# sd2_redraw.net
KiCad netlist of a schematic drawn in EAGLE
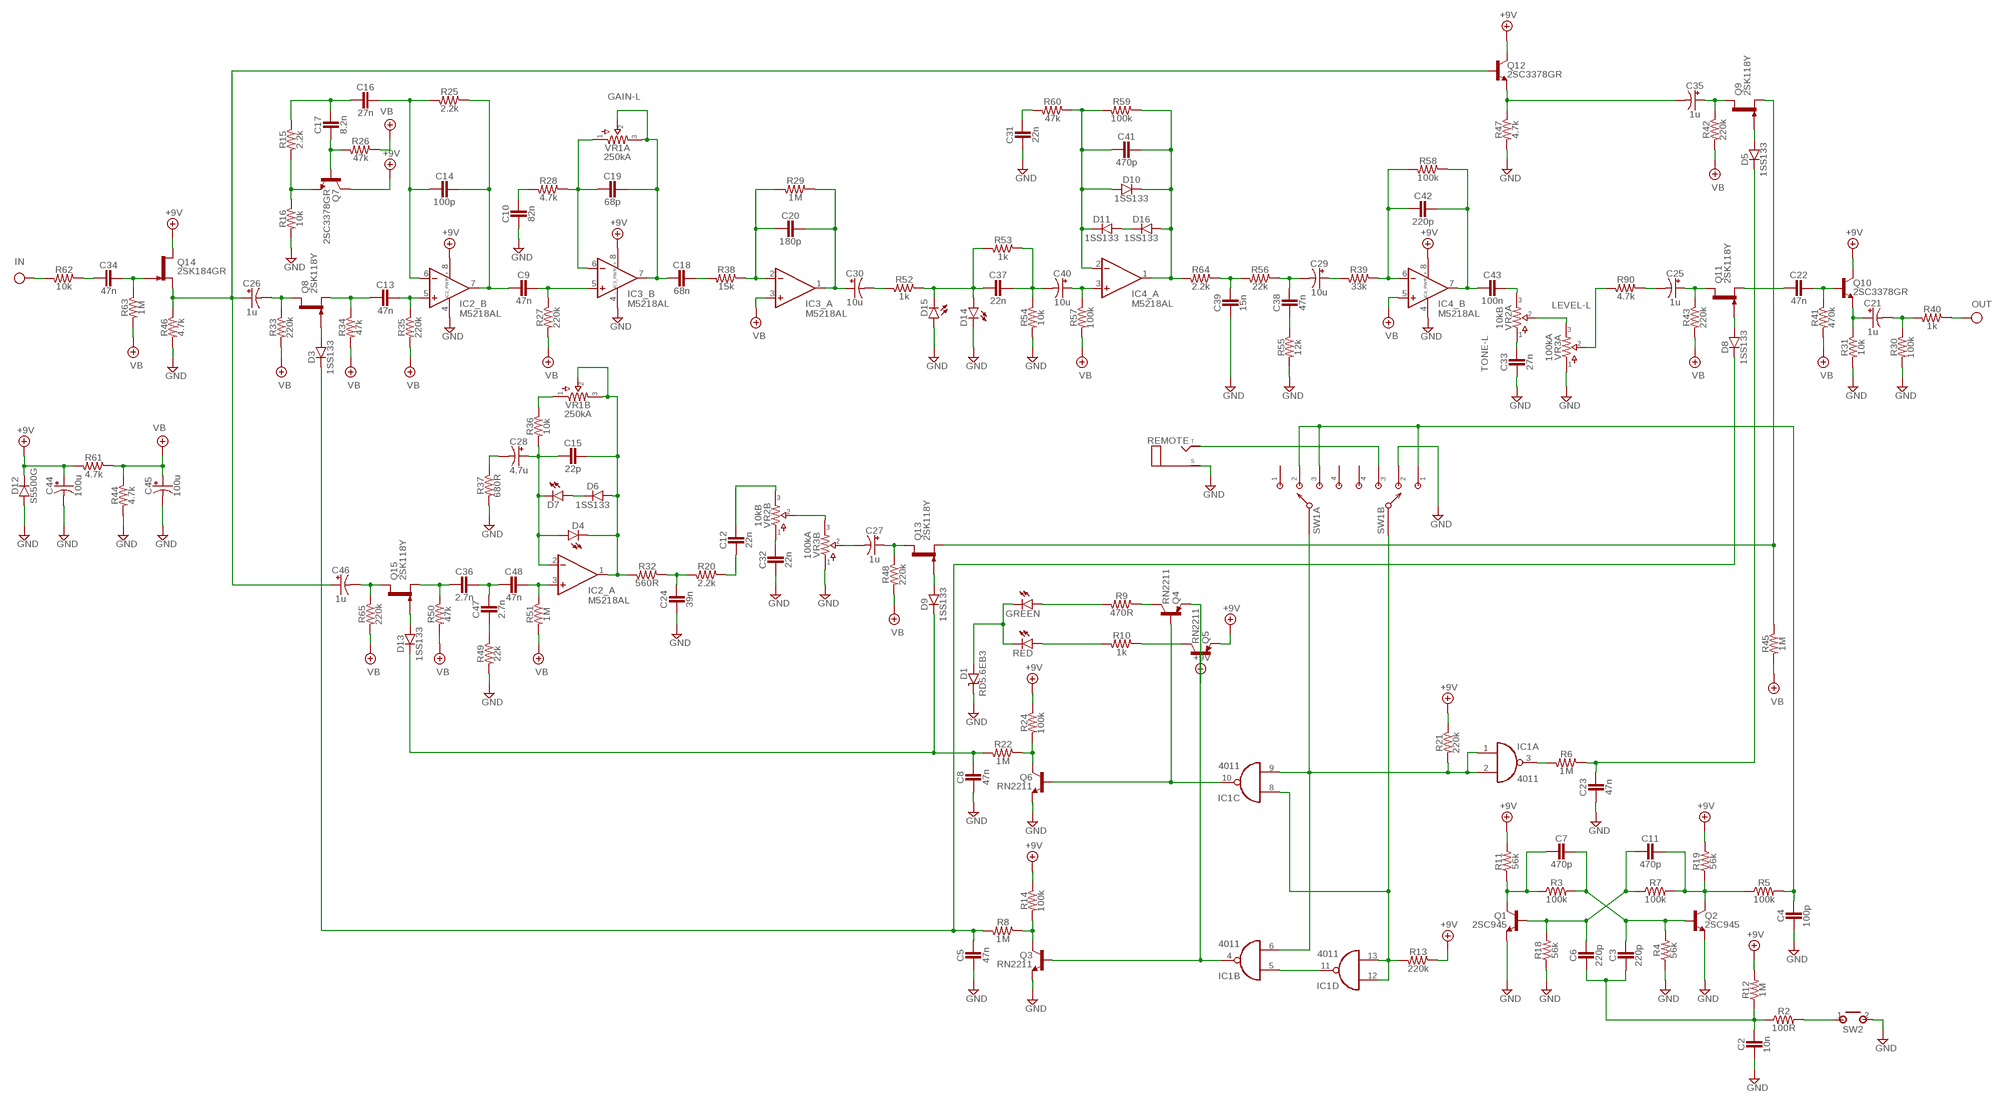
[diagram p0: schematic, sheet 1]

(export (version "E")
  (design (tool "Eeschema 10.0.6"))
  (components
    (comp (ref "C2")
      (value "10n")
      (footprint "eagle-import:BOX_SMALL")
      (libsource (lib "eagle-import") (part "CER/FILMBOX.1"))
    )
    (comp (ref "C3")
      (value "220p")
      (footprint "eagle-import:BOX_SMALL")
      (libsource (lib "eagle-import") (part "CER/FILMBOX.1"))
    )
    (comp (ref "C4")
      (value "100p")
      (footprint "eagle-import:BOX_SMALL")
      (libsource (lib "eagle-import") (part "CER/FILMBOX.1"))
    )
    (comp (ref "C5")
      (value "47n")
      (footprint "eagle-import:BOX_SMALL")
      (libsource (lib "eagle-import") (part "CER/FILMBOX.1"))
    )
    (comp (ref "C6")
      (value "220p")
      (footprint "eagle-import:BOX_SMALL")
      (libsource (lib "eagle-import") (part "CER/FILMBOX.1"))
    )
    (comp (ref "C7")
      (value "470p")
      (footprint "eagle-import:BOX_SMALL")
      (libsource (lib "eagle-import") (part "CER/FILMBOX.1"))
    )
    (comp (ref "C8")
      (value "47n")
      (footprint "eagle-import:BOX_SMALL")
      (libsource (lib "eagle-import") (part "CER/FILMBOX.1"))
    )
    (comp (ref "C9")
      (value "47n")
      (footprint "eagle-import:BOX_SMALL")
      (libsource (lib "eagle-import") (part "CER/FILMBOX.1"))
    )
    (comp (ref "C10")
      (value "82n")
      (footprint "eagle-import:BOX_SMALL")
      (libsource (lib "eagle-import") (part "CER/FILMBOX.1"))
    )
    (comp (ref "C11")
      (value "470p")
      (footprint "eagle-import:BOX_SMALL")
      (libsource (lib "eagle-import") (part "CER/FILMBOX.1"))
    )
    (comp (ref "C12")
      (value "22n")
      (footprint "eagle-import:BOX_SMALL")
      (libsource (lib "eagle-import") (part "CER/FILMBOX.1"))
    )
    (comp (ref "C13")
      (value "47n")
      (footprint "eagle-import:BOX_SMALL")
      (libsource (lib "eagle-import") (part "CER/FILMBOX.1"))
    )
    (comp (ref "C14")
      (value "100p")
      (footprint "eagle-import:BOX_SMALL")
      (libsource (lib "eagle-import") (part "CER/FILMBOX.1"))
    )
    (comp (ref "C15")
      (value "22p")
      (footprint "eagle-import:BOX_SMALL")
      (libsource (lib "eagle-import") (part "CER/FILMBOX.1"))
    )
    (comp (ref "C16")
      (value "27n")
      (footprint "eagle-import:BOX_SMALL")
      (libsource (lib "eagle-import") (part "CER/FILMBOX.1"))
    )
    (comp (ref "C17")
      (value "8.2n")
      (footprint "eagle-import:BOX_SMALL")
      (libsource (lib "eagle-import") (part "CER/FILMBOX.1"))
    )
    (comp (ref "C18")
      (value "68n")
      (footprint "eagle-import:BOX_SMALL")
      (libsource (lib "eagle-import") (part "CER/FILMBOX.1"))
    )
    (comp (ref "C19")
      (value "68p")
      (footprint "eagle-import:BOX_SMALL")
      (libsource (lib "eagle-import") (part "CER/FILMBOX.1"))
    )
    (comp (ref "C20")
      (value "180p")
      (footprint "eagle-import:BOX_SMALL")
      (libsource (lib "eagle-import") (part "CER/FILMBOX.1"))
    )
    (comp (ref "C21")
      (value "1u")
      (footprint "eagle-import:040_020")
      (libsource (lib "eagle-import") (part "0400"))
    )
    (comp (ref "C22")
      (value "47n")
      (footprint "eagle-import:BOX_SMALL")
      (libsource (lib "eagle-import") (part "CER/FILMBOX.1"))
    )
    (comp (ref "C23")
      (value "47n")
      (footprint "eagle-import:BOX_SMALL")
      (libsource (lib "eagle-import") (part "CER/FILMBOX.1"))
    )
    (comp (ref "C24")
      (value "39n")
      (footprint "eagle-import:BOX_SMALL")
      (libsource (lib "eagle-import") (part "CER/FILMBOX.1"))
    )
    (comp (ref "C25")
      (value "1u")
      (footprint "eagle-import:040_020")
      (libsource (lib "eagle-import") (part "0400"))
    )
    (comp (ref "C26")
      (value "1u")
      (footprint "eagle-import:040_020")
      (libsource (lib "eagle-import") (part "0400"))
    )
    (comp (ref "C27")
      (value "1u")
      (footprint "eagle-import:040_020")
      (libsource (lib "eagle-import") (part "0400"))
    )
    (comp (ref "C28")
      (value "4.7u")
      (footprint "eagle-import:040_020")
      (libsource (lib "eagle-import") (part "0400"))
    )
    (comp (ref "C29")
      (value "10u")
      (footprint "eagle-import:040_020")
      (libsource (lib "eagle-import") (part "0400"))
    )
    (comp (ref "C30")
      (value "10u")
      (footprint "eagle-import:040_020")
      (libsource (lib "eagle-import") (part "0400"))
    )
    (comp (ref "C31")
      (value "22n")
      (footprint "eagle-import:BOX_SMALL")
      (libsource (lib "eagle-import") (part "CER/FILMBOX.1"))
    )
    (comp (ref "C32")
      (value "22n")
      (footprint "eagle-import:BOX_SMALL")
      (libsource (lib "eagle-import") (part "CER/FILMBOX.1"))
    )
    (comp (ref "C33")
      (value "27n")
      (footprint "eagle-import:BOX_SMALL")
      (libsource (lib "eagle-import") (part "CER/FILMBOX.1"))
    )
    (comp (ref "C34")
      (value "47n")
      (footprint "eagle-import:BOX_SMALL")
      (libsource (lib "eagle-import") (part "CER/FILMBOX.1"))
    )
    (comp (ref "C35")
      (value "1u")
      (footprint "eagle-import:040_020")
      (libsource (lib "eagle-import") (part "0400"))
    )
    (comp (ref "C36")
      (value "2.7n")
      (footprint "eagle-import:BOX_SMALL")
      (libsource (lib "eagle-import") (part "CER/FILMBOX.1"))
    )
    (comp (ref "C37")
      (value "22n")
      (footprint "eagle-import:BOX_SMALL")
      (libsource (lib "eagle-import") (part "CER/FILMBOX.1"))
    )
    (comp (ref "C38")
      (value "47n")
      (footprint "eagle-import:BOX_SMALL")
      (libsource (lib "eagle-import") (part "CER/FILMBOX.1"))
    )
    (comp (ref "C39")
      (value "15n")
      (footprint "eagle-import:BOX_SMALL")
      (libsource (lib "eagle-import") (part "CER/FILMBOX.1"))
    )
    (comp (ref "C40")
      (value "10u")
      (footprint "eagle-import:040_020")
      (libsource (lib "eagle-import") (part "0400"))
    )
    (comp (ref "C41")
      (value "470p")
      (footprint "eagle-import:BOX_SMALL")
      (libsource (lib "eagle-import") (part "CER/FILMBOX.1"))
    )
    (comp (ref "C42")
      (value "220p")
      (footprint "eagle-import:BOX_SMALL")
      (libsource (lib "eagle-import") (part "CER/FILMBOX.1"))
    )
    (comp (ref "C43")
      (value "100n")
      (footprint "eagle-import:BOX_SMALL")
      (libsource (lib "eagle-import") (part "CER/FILMBOX.1"))
    )
    (comp (ref "C44")
      (value "100u")
      (footprint "eagle-import:040_020")
      (libsource (lib "eagle-import") (part "0400"))
    )
    (comp (ref "C45")
      (value "100u")
      (footprint "eagle-import:040_020")
      (libsource (lib "eagle-import") (part "0400"))
    )
    (comp (ref "C46")
      (value "1u")
      (footprint "eagle-import:040_020")
      (libsource (lib "eagle-import") (part "0400"))
    )
    (comp (ref "C47")
      (value "2.7n")
      (footprint "eagle-import:BOX_SMALL")
      (libsource (lib "eagle-import") (part "CER/FILMBOX.1"))
    )
    (comp (ref "C48")
      (value "47n")
      (footprint "eagle-import:BOX_SMALL")
      (libsource (lib "eagle-import") (part "CER/FILMBOX.1"))
    )
    (comp (ref "D1")
      (value "RD5.6EB3")
      (footprint "eagle-import:DO41-2")
      (libsource (lib "eagle-import") (part "ZENER.2"))
    )
    (comp (ref "D3")
      (value "1SS133")
      (footprint "eagle-import:DO35-2")
      (libsource (lib "eagle-import") (part "DO35.2"))
    )
    (comp (ref "D4")
      (value "LED")
      (footprint "eagle-import:3MM_D")
      (libsource (lib "eagle-import") (part "LED"))
    )
    (comp (ref "D5")
      (value "1SS133")
      (footprint "eagle-import:DO35-2")
      (libsource (lib "eagle-import") (part "DO35.2"))
    )
    (comp (ref "D6")
      (value "1SS133")
      (footprint "eagle-import:DO35-2")
      (libsource (lib "eagle-import") (part "DO35.2"))
    )
    (comp (ref "D7")
      (value "LED")
      (footprint "eagle-import:3MM_D")
      (libsource (lib "eagle-import") (part "LED"))
    )
    (comp (ref "D8")
      (value "1SS133")
      (footprint "eagle-import:DO35-2")
      (libsource (lib "eagle-import") (part "DO35.2"))
    )
    (comp (ref "D9")
      (value "1SS133")
      (footprint "eagle-import:DO35-2")
      (libsource (lib "eagle-import") (part "DO35.2"))
    )
    (comp (ref "D10")
      (value "1SS133")
      (footprint "eagle-import:DO35-2")
      (libsource (lib "eagle-import") (part "DO35.2"))
    )
    (comp (ref "D11")
      (value "1SS133")
      (footprint "eagle-import:DO35-2")
      (libsource (lib "eagle-import") (part "DO35.2"))
    )
    (comp (ref "D12")
      (value "S5500G")
      (footprint "eagle-import:DO35-2")
      (libsource (lib "eagle-import") (part "DO35.2"))
    )
    (comp (ref "D13")
      (value "1SS133")
      (footprint "eagle-import:DO35-2")
      (libsource (lib "eagle-import") (part "DO35.2"))
    )
    (comp (ref "D14")
      (value "LED")
      (footprint "eagle-import:3MM_D")
      (libsource (lib "eagle-import") (part "LED"))
    )
    (comp (ref "D15")
      (value "LED")
      (footprint "eagle-import:3MM_D")
      (libsource (lib "eagle-import") (part "LED"))
    )
    (comp (ref "D16")
      (value "1SS133")
      (footprint "eagle-import:DO35-2")
      (libsource (lib "eagle-import") (part "DO35.2"))
    )
    (comp (ref "GREEN")
      (value "LED")
      (footprint "eagle-import:3MM_D")
      (libsource (lib "eagle-import") (part "LED"))
    )
    (comp (ref "IC1")
      (value "4011")
      (footprint "eagle-import:DIL14")
      (libsource (lib "eagle-import") (part "4011N"))
    )
    (comp (ref "IC2")
      (value "M5218AL")
      (footprint "eagle-import:DIL0")
      (libsource (lib "eagle-import") (part "DUALTH"))
    )
    (comp (ref "IC3")
      (value "M5218AL")
      (footprint "eagle-import:DIL0")
      (libsource (lib "eagle-import") (part "DUALTH"))
    )
    (comp (ref "IC4")
      (value "M5218AL")
      (footprint "eagle-import:DIL0")
      (libsource (lib "eagle-import") (part "DUALTH"))
    )
    (comp (ref "Q1")
      (value "2SC945")
      (footprint "eagle-import:TO92-")
      (libsource (lib "eagle-import") (part "2SC828A"))
    )
    (comp (ref "Q2")
      (value "2SC945")
      (footprint "eagle-import:TO92-")
      (libsource (lib "eagle-import") (part "2SC828A"))
    )
    (comp (ref "Q3")
      (value "RN2211")
      (footprint "eagle-import:TO92-")
      (libsource (lib "eagle-import") (part "2N3904"))
    )
    (comp (ref "Q4")
      (value "RN2211")
      (footprint "eagle-import:TO92")
      (libsource (lib "eagle-import") (part "2N3906"))
    )
    (comp (ref "Q5")
      (value "RN2211")
      (footprint "eagle-import:TO92")
      (libsource (lib "eagle-import") (part "2N3906"))
    )
    (comp (ref "Q6")
      (value "RN2211")
      (footprint "eagle-import:TO92-")
      (libsource (lib "eagle-import") (part "2N3904"))
    )
    (comp (ref "Q7")
      (value "2SC3378GR")
      (footprint "eagle-import:TO92-")
      (libsource (lib "eagle-import") (part "2N3904"))
    )
    (comp (ref "Q8")
      (value "2SK118Y")
      (footprint "eagle-import:TO92-")
      (libsource (lib "eagle-import") (part "2N5457"))
    )
    (comp (ref "Q9")
      (value "2SK118Y")
      (footprint "eagle-import:TO92-")
      (libsource (lib "eagle-import") (part "2N5457"))
    )
    (comp (ref "Q10")
      (value "2SC3378GR")
      (footprint "eagle-import:TO92-")
      (libsource (lib "eagle-import") (part "2N3904"))
    )
    (comp (ref "Q11")
      (value "2SK118Y")
      (footprint "eagle-import:TO92-")
      (libsource (lib "eagle-import") (part "2N5457"))
    )
    (comp (ref "Q12")
      (value "2SC3378GR")
      (footprint "eagle-import:TO92-")
      (libsource (lib "eagle-import") (part "2N3904"))
    )
    (comp (ref "Q13")
      (value "2SK118Y")
      (footprint "eagle-import:TO92-")
      (libsource (lib "eagle-import") (part "2N5457"))
    )
    (comp (ref "Q14")
      (value "2SK184GR")
      (footprint "eagle-import:TO92-")
      (libsource (lib "eagle-import") (part "2N5457"))
    )
    (comp (ref "Q15")
      (value "2SK118Y")
      (footprint "eagle-import:TO92-")
      (libsource (lib "eagle-import") (part "2N5457"))
    )
    (comp (ref "R2")
      (value "100R")
      (footprint "eagle-import:R0207_3")
      (libsource (lib "eagle-import") (part "R_.3B"))
    )
    (comp (ref "R3")
      (value "100k")
      (footprint "eagle-import:R0207_3")
      (libsource (lib "eagle-import") (part "R_.3B"))
    )
    (comp (ref "R4")
      (value "56k")
      (footprint "eagle-import:R0207_3")
      (libsource (lib "eagle-import") (part "R_.3B"))
    )
    (comp (ref "R5")
      (value "100k")
      (footprint "eagle-import:R0207_3")
      (libsource (lib "eagle-import") (part "R_.3B"))
    )
    (comp (ref "R6")
      (value "1M")
      (footprint "eagle-import:R0207_3")
      (libsource (lib "eagle-import") (part "R_.3B"))
    )
    (comp (ref "R7")
      (value "100k")
      (footprint "eagle-import:R0207_3")
      (libsource (lib "eagle-import") (part "R_.3B"))
    )
    (comp (ref "R8")
      (value "1M")
      (footprint "eagle-import:R0207_3")
      (libsource (lib "eagle-import") (part "R_.3B"))
    )
    (comp (ref "R9")
      (value "470R")
      (footprint "eagle-import:R0207_3")
      (libsource (lib "eagle-import") (part "R_.3B"))
    )
    (comp (ref "R10")
      (value "1k")
      (footprint "eagle-import:R0207_3")
      (libsource (lib "eagle-import") (part "R_.3B"))
    )
    (comp (ref "R11")
      (value "56k")
      (footprint "eagle-import:R0207_3")
      (libsource (lib "eagle-import") (part "R_.3B"))
    )
    (comp (ref "R12")
      (value "1M")
      (footprint "eagle-import:R0207_3")
      (libsource (lib "eagle-import") (part "R_.3B"))
    )
    (comp (ref "R13")
      (value "220k")
      (footprint "eagle-import:R0207_3")
      (libsource (lib "eagle-import") (part "R_.3B"))
    )
    (comp (ref "R14")
      (value "100k")
      (footprint "eagle-import:R0207_3")
      (libsource (lib "eagle-import") (part "R_.3B"))
    )
    (comp (ref "R15")
      (value "2.2k")
      (footprint "eagle-import:R0207_3")
      (libsource (lib "eagle-import") (part "R_.3B"))
    )
    (comp (ref "R16")
      (value "10k")
      (footprint "eagle-import:R0207_3")
      (libsource (lib "eagle-import") (part "R_.3B"))
    )
    (comp (ref "R18")
      (value "56k")
      (footprint "eagle-import:R0207_3")
      (libsource (lib "eagle-import") (part "R_.3B"))
    )
    (comp (ref "R19")
      (value "56k")
      (footprint "eagle-import:R0207_3")
      (libsource (lib "eagle-import") (part "R_.3B"))
    )
    (comp (ref "R20")
      (value "2.2k")
      (footprint "eagle-import:R0207_3")
      (libsource (lib "eagle-import") (part "R_.3B"))
    )
    (comp (ref "R21")
      (value "220k")
      (footprint "eagle-import:R0207_3")
      (libsource (lib "eagle-import") (part "R_.3B"))
    )
    (comp (ref "R22")
      (value "1M")
      (footprint "eagle-import:R0207_3")
      (libsource (lib "eagle-import") (part "R_.3B"))
    )
    (comp (ref "R24")
      (value "100k")
      (footprint "eagle-import:R0207_3")
      (libsource (lib "eagle-import") (part "R_.3B"))
    )
    (comp (ref "R25")
      (value "2.2k")
      (footprint "eagle-import:R0207_3")
      (libsource (lib "eagle-import") (part "R_.3B"))
    )
    (comp (ref "R26")
      (value "47k")
      (footprint "eagle-import:R0207_3")
      (libsource (lib "eagle-import") (part "R_.3B"))
    )
    (comp (ref "R27")
      (value "220k")
      (footprint "eagle-import:R0207_3")
      (libsource (lib "eagle-import") (part "R_.3B"))
    )
    (comp (ref "R28")
      (value "4.7k")
      (footprint "eagle-import:R0207_3")
      (libsource (lib "eagle-import") (part "R_.3B"))
    )
    (comp (ref "R29")
      (value "1M")
      (footprint "eagle-import:R0207_3")
      (libsource (lib "eagle-import") (part "R_.3B"))
    )
    (comp (ref "R30")
      (value "100k")
      (footprint "eagle-import:R0207_3")
      (libsource (lib "eagle-import") (part "R_.3B"))
    )
    (comp (ref "R31")
      (value "10k")
      (footprint "eagle-import:R0207_3")
      (libsource (lib "eagle-import") (part "R_.3B"))
    )
    (comp (ref "R32")
      (value "560R")
      (footprint "eagle-import:R0207_3")
      (libsource (lib "eagle-import") (part "R_.3B"))
    )
    (comp (ref "R33")
      (value "220k")
      (footprint "eagle-import:R0207_3")
      (libsource (lib "eagle-import") (part "R_.3B"))
    )
    (comp (ref "R34")
      (value "47k")
      (footprint "eagle-import:R0207_3")
      (libsource (lib "eagle-import") (part "R_.3B"))
    )
    (comp (ref "R35")
      (value "220k")
      (footprint "eagle-import:R0207_3")
      (libsource (lib "eagle-import") (part "R_.3B"))
    )
    (comp (ref "R36")
      (value "10k")
      (footprint "eagle-import:R0207_3")
      (libsource (lib "eagle-import") (part "R_.3B"))
    )
    (comp (ref "R37")
      (value "680R")
      (footprint "eagle-import:R0207_3")
      (libsource (lib "eagle-import") (part "R_.3B"))
    )
    (comp (ref "R38")
      (value "15k")
      (footprint "eagle-import:R0207_3")
      (libsource (lib "eagle-import") (part "R_.3B"))
    )
    (comp (ref "R39")
      (value "33k")
      (footprint "eagle-import:R0207_3")
      (libsource (lib "eagle-import") (part "R_.3B"))
    )
    (comp (ref "R40")
      (value "1k")
      (footprint "eagle-import:R0207_3")
      (libsource (lib "eagle-import") (part "R_.3B"))
    )
    (comp (ref "R41")
      (value "470k")
      (footprint "eagle-import:R0207_3")
      (libsource (lib "eagle-import") (part "R_.3B"))
    )
    (comp (ref "R42")
      (value "220k")
      (footprint "eagle-import:R0207_3")
      (libsource (lib "eagle-import") (part "R_.3B"))
    )
    (comp (ref "R43")
      (value "220k")
      (footprint "eagle-import:R0207_3")
      (libsource (lib "eagle-import") (part "R_.3B"))
    )
    (comp (ref "R44")
      (value "4.7k")
      (footprint "eagle-import:R0207_3")
      (libsource (lib "eagle-import") (part "R_.3B"))
    )
    (comp (ref "R45")
      (value "1M")
      (footprint "eagle-import:R0207_3")
      (libsource (lib "eagle-import") (part "R_.3B"))
    )
    (comp (ref "R46")
      (value "4.7k")
      (footprint "eagle-import:R0207_3")
      (libsource (lib "eagle-import") (part "R_.3B"))
    )
    (comp (ref "R47")
      (value "4.7k")
      (footprint "eagle-import:R0207_3")
      (libsource (lib "eagle-import") (part "R_.3B"))
    )
    (comp (ref "R48")
      (value "220k")
      (footprint "eagle-import:R0207_3")
      (libsource (lib "eagle-import") (part "R_.3B"))
    )
    (comp (ref "R49")
      (value "22k")
      (footprint "eagle-import:R0207_3")
      (libsource (lib "eagle-import") (part "R_.3B"))
    )
    (comp (ref "R50")
      (value "47k")
      (footprint "eagle-import:R0207_3")
      (libsource (lib "eagle-import") (part "R_.3B"))
    )
    (comp (ref "R51")
      (value "1M")
      (footprint "eagle-import:R0207_3")
      (libsource (lib "eagle-import") (part "R_.3B"))
    )
    (comp (ref "R52")
      (value "1k")
      (footprint "eagle-import:R0207_3")
      (libsource (lib "eagle-import") (part "R_.3B"))
    )
    (comp (ref "R53")
      (value "1k")
      (footprint "eagle-import:R0207_3")
      (libsource (lib "eagle-import") (part "R_.3B"))
    )
    (comp (ref "R54")
      (value "10k")
      (footprint "eagle-import:R0207_3")
      (libsource (lib "eagle-import") (part "R_.3B"))
    )
    (comp (ref "R55")
      (value "12k")
      (footprint "eagle-import:R0207_3")
      (libsource (lib "eagle-import") (part "R_.3B"))
    )
    (comp (ref "R56")
      (value "22k")
      (footprint "eagle-import:R0207_3")
      (libsource (lib "eagle-import") (part "R_.3B"))
    )
    (comp (ref "R57")
      (value "100k")
      (footprint "eagle-import:R0207_3")
      (libsource (lib "eagle-import") (part "R_.3B"))
    )
    (comp (ref "R58")
      (value "100k")
      (footprint "eagle-import:R0207_3")
      (libsource (lib "eagle-import") (part "R_.3B"))
    )
    (comp (ref "R59")
      (value "100k")
      (footprint "eagle-import:R0207_3")
      (libsource (lib "eagle-import") (part "R_.3B"))
    )
    (comp (ref "R60")
      (value "47k")
      (footprint "eagle-import:R0207_3")
      (libsource (lib "eagle-import") (part "R_.3B"))
    )
    (comp (ref "R61")
      (value "4.7k")
      (footprint "eagle-import:R0207_3")
      (libsource (lib "eagle-import") (part "R_.3B"))
    )
    (comp (ref "R62")
      (value "10k")
      (footprint "eagle-import:R0207_3")
      (libsource (lib "eagle-import") (part "R_.3B"))
    )
    (comp (ref "R63")
      (value "1M")
      (footprint "eagle-import:R0207_3")
      (libsource (lib "eagle-import") (part "R_.3B"))
    )
    (comp (ref "R64")
      (value "2.2k")
      (footprint "eagle-import:R0207_3")
      (libsource (lib "eagle-import") (part "R_.3B"))
    )
    (comp (ref "R65")
      (value "220k")
      (footprint "eagle-import:R0207_3")
      (libsource (lib "eagle-import") (part "R_.3B"))
    )
    (comp (ref "R90")
      (value "4.7k")
      (footprint "eagle-import:R0207_3")
      (libsource (lib "eagle-import") (part "R_.3B"))
    )
    (comp (ref "RED")
      (value "LED")
      (footprint "eagle-import:3MM_D")
      (libsource (lib "eagle-import") (part "LED"))
    )
    (comp (ref "REMOTE")
      (value "MONO")
      (footprint "eagle-import:TWO_PADS")
      (libsource (lib "eagle-import") (part "MONO"))
    )
    (comp (ref "SW1")
      (value "2P4T")
      (footprint "eagle-import:SMALLROTARY")
      (libsource (lib "eagle-import") (part "2P4T"))
    )
    (comp (ref "SW2")
      (value "MOMENTARY")
      (footprint "eagle-import:SPST")
      (libsource (lib "eagle-import") (part "MOMENTARY"))
    )
    (comp (ref "VR1A")
      (value "250kA")
      (footprint "eagle-import:16MM")
      (libsource (lib "eagle-import") (part "POTS16MM"))
    )
    (comp (ref "VR1B")
      (value "250kA")
      (footprint "eagle-import:16MM")
      (libsource (lib "eagle-import") (part "POTS16MM"))
    )
    (comp (ref "VR2A")
      (value "10kB")
      (footprint "eagle-import:16MM")
      (libsource (lib "eagle-import") (part "POTS16MM"))
    )
    (comp (ref "VR2B")
      (value "10kB")
      (footprint "eagle-import:16MM")
      (libsource (lib "eagle-import") (part "POTS16MM"))
    )
    (comp (ref "VR3A")
      (value "100kA")
      (footprint "eagle-import:16MM")
      (libsource (lib "eagle-import") (part "POTS16MM"))
    )
    (comp (ref "VR3B")
      (value "100kA")
      (footprint "eagle-import:16MM")
      (libsource (lib "eagle-import") (part "POTS16MM"))
    )
  )
  (nets
    (net (code "1") (name "+9V") (class "Default")
      (node (ref "C44") (pin "+") (pinfunction "+_+") (pintype "passive"))
      (node (ref "D12") (pin "C") (pinfunction "C_C") (pintype "passive"))
      (node (ref "IC2") (pin "8") (pinfunction "V+_8") (pintype "power_in"))
      (node (ref "IC3") (pin "8") (pinfunction "V+_8") (pintype "power_in"))
      (node (ref "IC4") (pin "8") (pinfunction "V+_8") (pintype "power_in"))
      (node (ref "Q10") (pin "1") (pinfunction "C_1") (pintype "passive"))
      (node (ref "Q12") (pin "1") (pinfunction "C_1") (pintype "passive"))
      (node (ref "Q14") (pin "3") (pinfunction "D_3") (pintype "passive"))
      (node (ref "Q4") (pin "3") (pinfunction "E_3") (pintype "passive"))
      (node (ref "Q5") (pin "3") (pinfunction "E_3") (pintype "passive"))
      (node (ref "Q7") (pin "1") (pinfunction "C_1") (pintype "passive"))
      (node (ref "R11") (pin "2") (pinfunction "2_2") (pintype "passive"))
      (node (ref "R12") (pin "2") (pinfunction "2_2") (pintype "passive"))
      (node (ref "R13") (pin "1") (pinfunction "1_1") (pintype "passive"))
      (node (ref "R14") (pin "1") (pinfunction "1_1") (pintype "passive"))
      (node (ref "R19") (pin "2") (pinfunction "2_2") (pintype "passive"))
      (node (ref "R21") (pin "1") (pinfunction "1_1") (pintype "passive"))
      (node (ref "R24") (pin "1") (pinfunction "1_1") (pintype "passive"))
      (node (ref "R61") (pin "2") (pinfunction "2_2") (pintype "passive"))
    )
    (net (code "2") (name "GND") (class "Default")
      (node (ref "C10") (pin "2") (pinfunction "2_2") (pintype "passive"))
      (node (ref "C2") (pin "2") (pinfunction "2_2") (pintype "passive"))
      (node (ref "C23") (pin "2") (pinfunction "2_2") (pintype "passive"))
      (node (ref "C24") (pin "2") (pinfunction "2_2") (pintype "passive"))
      (node (ref "C31") (pin "2") (pinfunction "2_2") (pintype "passive"))
      (node (ref "C32") (pin "2") (pinfunction "2_2") (pintype "passive"))
      (node (ref "C33") (pin "2") (pinfunction "2_2") (pintype "passive"))
      (node (ref "C39") (pin "2") (pinfunction "2_2") (pintype "passive"))
      (node (ref "C4") (pin "2") (pinfunction "2_2") (pintype "passive"))
      (node (ref "C44") (pin "-") (pinfunction "-_-") (pintype "passive"))
      (node (ref "C45") (pin "-") (pinfunction "-_-") (pintype "passive"))
      (node (ref "C5") (pin "2") (pinfunction "2_2") (pintype "passive"))
      (node (ref "C8") (pin "2") (pinfunction "2_2") (pintype "passive"))
      (node (ref "D1") (pin "C") (pinfunction "C_C") (pintype "passive"))
      (node (ref "D12") (pin "A") (pinfunction "A_A") (pintype "passive"))
      (node (ref "D14") (pin "P$1") (pinfunction "C_P$1") (pintype "passive"))
      (node (ref "D15") (pin "ANODE") (pinfunction "A_ANODE") (pintype "passive"))
      (node (ref "IC2") (pin "4") (pinfunction "V-_4") (pintype "power_in"))
      (node (ref "IC3") (pin "4") (pinfunction "V-_4") (pintype "power_in"))
      (node (ref "IC4") (pin "4") (pinfunction "V-_4") (pintype "power_in"))
      (node (ref "Q1") (pin "3") (pinfunction "E_3") (pintype "passive"))
      (node (ref "Q2") (pin "3") (pinfunction "E_3") (pintype "passive"))
      (node (ref "Q3") (pin "3") (pinfunction "E_3") (pintype "passive"))
      (node (ref "Q6") (pin "3") (pinfunction "E_3") (pintype "passive"))
      (node (ref "R16") (pin "2") (pinfunction "2_2") (pintype "passive"))
      (node (ref "R18") (pin "1") (pinfunction "1_1") (pintype "passive"))
      (node (ref "R30") (pin "2") (pinfunction "2_2") (pintype "passive"))
      (node (ref "R31") (pin "2") (pinfunction "2_2") (pintype "passive"))
      (node (ref "R37") (pin "2") (pinfunction "2_2") (pintype "passive"))
      (node (ref "R4") (pin "1") (pinfunction "1_1") (pintype "passive"))
      (node (ref "R44") (pin "2") (pinfunction "2_2") (pintype "passive"))
      (node (ref "R46") (pin "2") (pinfunction "2_2") (pintype "passive"))
      (node (ref "R47") (pin "2") (pinfunction "2_2") (pintype "passive"))
      (node (ref "R49") (pin "2") (pinfunction "2_2") (pintype "passive"))
      (node (ref "R54") (pin "2") (pinfunction "2_2") (pintype "passive"))
      (node (ref "R55") (pin "2") (pinfunction "2_2") (pintype "passive"))
      (node (ref "REMOTE") (pin "S") (pinfunction "SLEEVE_S") (pintype "passive"))
      (node (ref "SW1") (pin "6") (pinfunction "2_6") (pintype "bidirectional"))
      (node (ref "SW2") (pin "2") (pinfunction "S_2") (pintype "passive"))
      (node (ref "VR3A") (pin "1") (pinfunction "1_1") (pintype "passive"))
      (node (ref "VR3B") (pin "1") (pinfunction "1_1") (pintype "passive"))
    )
    (net (code "3") (name "IN") (class "Default")
      (node (ref "R62") (pin "2") (pinfunction "2_2") (pintype "passive"))
    )
    (net (code "4") (name "Net-(C2-Pad1)") (class "Default")
      (node (ref "C2") (pin "1") (pinfunction "1_1") (pintype "passive"))
      (node (ref "C3") (pin "2") (pinfunction "2_2") (pintype "passive"))
      (node (ref "C6") (pin "2") (pinfunction "2_2") (pintype "passive"))
      (node (ref "R12") (pin "1") (pinfunction "1_1") (pintype "passive"))
      (node (ref "R2") (pin "1") (pinfunction "1_1") (pintype "passive"))
    )
    (net (code "5") (name "Net-(C5-Pad1)") (class "Default")
      (node (ref "C5") (pin "1") (pinfunction "1_1") (pintype "passive"))
      (node (ref "D3") (pin "C") (pinfunction "C_C") (pintype "passive"))
      (node (ref "D8") (pin "C") (pinfunction "C_C") (pintype "passive"))
      (node (ref "R8") (pin "2") (pinfunction "2_2") (pintype "passive"))
    )
    (net (code "6") (name "Net-(C8-Pad1)") (class "Default")
      (node (ref "C8") (pin "1") (pinfunction "1_1") (pintype "passive"))
      (node (ref "D13") (pin "C") (pinfunction "C_C") (pintype "passive"))
      (node (ref "D9") (pin "C") (pinfunction "C_C") (pintype "passive"))
      (node (ref "R22") (pin "2") (pinfunction "2_2") (pintype "passive"))
    )
    (net (code "7") (name "Net-(C10-Pad1)") (class "Default")
      (node (ref "C10") (pin "1") (pinfunction "1_1") (pintype "passive"))
      (node (ref "R28") (pin "2") (pinfunction "2_2") (pintype "passive"))
    )
    (net (code "8") (name "Net-(C12-Pad1)") (class "Default")
      (node (ref "C12") (pin "1") (pinfunction "1_1") (pintype "passive"))
      (node (ref "VR2B") (pin "3") (pinfunction "3_3") (pintype "passive"))
    )
    (net (code "9") (name "Net-(C12-Pad2)") (class "Default")
      (node (ref "C12") (pin "2") (pinfunction "2_2") (pintype "passive"))
      (node (ref "R20") (pin "1") (pinfunction "1_1") (pintype "passive"))
    )
    (net (code "10") (name "Net-(C16-Pad2)") (class "Default")
      (node (ref "C16") (pin "2") (pinfunction "2_2") (pintype "passive"))
      (node (ref "C17") (pin "1") (pinfunction "1_1") (pintype "passive"))
      (node (ref "R15") (pin "1") (pinfunction "1_1") (pintype "passive"))
    )
    (net (code "11") (name "Net-(C18-Pad1)") (class "Default")
      (node (ref "C18") (pin "1") (pinfunction "1_1") (pintype "passive"))
      (node (ref "R38") (pin "2") (pinfunction "2_2") (pintype "passive"))
    )
    (net (code "12") (name "Net-(C21-Pad-)") (class "Default")
      (node (ref "C21") (pin "-") (pinfunction "-_-") (pintype "passive"))
      (node (ref "R30") (pin "1") (pinfunction "1_1") (pintype "passive"))
      (node (ref "R40") (pin "2") (pinfunction "2_2") (pintype "passive"))
    )
    (net (code "13") (name "Net-(C23-Pad1)") (class "Default")
      (node (ref "C23") (pin "1") (pinfunction "1_1") (pintype "passive"))
      (node (ref "D5") (pin "C") (pinfunction "C_C") (pintype "passive"))
      (node (ref "R6") (pin "1") (pinfunction "1_1") (pintype "passive"))
    )
    (net (code "14") (name "Net-(C24-Pad1)") (class "Default")
      (node (ref "C24") (pin "1") (pinfunction "1_1") (pintype "passive"))
      (node (ref "R20") (pin "2") (pinfunction "2_2") (pintype "passive"))
      (node (ref "R32") (pin "1") (pinfunction "1_1") (pintype "passive"))
    )
    (net (code "15") (name "Net-(C25-Pad-)") (class "Default")
      (node (ref "C25") (pin "-") (pinfunction "-_-") (pintype "passive"))
      (node (ref "R90") (pin "1") (pinfunction "1_1") (pintype "passive"))
    )
    (net (code "16") (name "Net-(C27-Pad-)") (class "Default")
      (node (ref "C27") (pin "-") (pinfunction "-_-") (pintype "passive"))
      (node (ref "VR3B") (pin "2") (pinfunction "2_2") (pintype "passive"))
    )
    (net (code "17") (name "Net-(C28-Pad-)") (class "Default")
      (node (ref "C28") (pin "-") (pinfunction "-_-") (pintype "passive"))
      (node (ref "R37") (pin "1") (pinfunction "1_1") (pintype "passive"))
    )
    (net (code "18") (name "Net-(C29-Pad+)") (class "Default")
      (node (ref "C29") (pin "+") (pinfunction "+_+") (pintype "passive"))
      (node (ref "R39") (pin "2") (pinfunction "2_2") (pintype "passive"))
    )
    (net (code "19") (name "Net-(C29-Pad-)") (class "Default")
      (node (ref "C29") (pin "-") (pinfunction "-_-") (pintype "passive"))
      (node (ref "C38") (pin "1") (pinfunction "1_1") (pintype "passive"))
      (node (ref "R56") (pin "1") (pinfunction "1_1") (pintype "passive"))
    )
    (net (code "20") (name "Net-(C30-Pad-)") (class "Default")
      (node (ref "C30") (pin "-") (pinfunction "-_-") (pintype "passive"))
      (node (ref "R52") (pin "2") (pinfunction "2_2") (pintype "passive"))
    )
    (net (code "21") (name "Net-(C31-Pad1)") (class "Default")
      (node (ref "C31") (pin "1") (pinfunction "1_1") (pintype "passive"))
      (node (ref "R60") (pin "2") (pinfunction "2_2") (pintype "passive"))
    )
    (net (code "22") (name "Net-(C32-Pad1)") (class "Default")
      (node (ref "C32") (pin "1") (pinfunction "1_1") (pintype "passive"))
      (node (ref "VR2B") (pin "1") (pinfunction "1_1") (pintype "passive"))
    )
    (net (code "23") (name "Net-(C33-Pad1)") (class "Default")
      (node (ref "C33") (pin "1") (pinfunction "1_1") (pintype "passive"))
      (node (ref "VR2A") (pin "1") (pinfunction "1_1") (pintype "passive"))
    )
    (net (code "24") (name "Net-(C34-Pad2)") (class "Default")
      (node (ref "C34") (pin "2") (pinfunction "2_2") (pintype "passive"))
      (node (ref "R62") (pin "1") (pinfunction "1_1") (pintype "passive"))
    )
    (net (code "25") (name "Net-(C36-Pad1)") (class "Default")
      (node (ref "C36") (pin "1") (pinfunction "1_1") (pintype "passive"))
      (node (ref "C47") (pin "1") (pinfunction "1_1") (pintype "passive"))
      (node (ref "C48") (pin "2") (pinfunction "2_2") (pintype "passive"))
    )
    (net (code "26") (name "Net-(C37-Pad1)") (class "Default")
      (node (ref "C37") (pin "1") (pinfunction "1_1") (pintype "passive"))
      (node (ref "C40") (pin "-") (pinfunction "-_-") (pintype "passive"))
      (node (ref "R53") (pin "1") (pinfunction "1_1") (pintype "passive"))
      (node (ref "R54") (pin "1") (pinfunction "1_1") (pintype "passive"))
    )
    (net (code "27") (name "Net-(C38-Pad2)") (class "Default")
      (node (ref "C38") (pin "2") (pinfunction "2_2") (pintype "passive"))
      (node (ref "R55") (pin "1") (pinfunction "1_1") (pintype "passive"))
    )
    (net (code "28") (name "Net-(C39-Pad1)") (class "Default")
      (node (ref "C39") (pin "1") (pinfunction "1_1") (pintype "passive"))
      (node (ref "R56") (pin "2") (pinfunction "2_2") (pintype "passive"))
      (node (ref "R64") (pin "1") (pinfunction "1_1") (pintype "passive"))
    )
    (net (code "29") (name "Net-(C43-Pad1)") (class "Default")
      (node (ref "C43") (pin "1") (pinfunction "1_1") (pintype "passive"))
      (node (ref "VR2A") (pin "3") (pinfunction "3_3") (pintype "passive"))
    )
    (net (code "30") (name "Net-(C47-Pad2)") (class "Default")
      (node (ref "C47") (pin "2") (pinfunction "2_2") (pintype "passive"))
      (node (ref "R49") (pin "1") (pinfunction "1_1") (pintype "passive"))
    )
    (net (code "31") (name "Net-(D4-A)") (class "Default")
      (node (ref "C15") (pin "2") (pinfunction "2_2") (pintype "passive"))
      (node (ref "C28") (pin "+") (pinfunction "+_+") (pintype "passive"))
      (node (ref "D4") (pin "ANODE") (pinfunction "A_ANODE") (pintype "passive"))
      (node (ref "D7") (pin "P$1") (pinfunction "C_P$1") (pintype "passive"))
      (node (ref "IC2") (pin "2") (pinfunction "-IN_2") (pintype "input"))
      (node (ref "R36") (pin "2") (pinfunction "2_2") (pintype "passive"))
    )
    (net (code "32") (name "Net-(D4-C)") (class "Default")
      (node (ref "C15") (pin "1") (pinfunction "1_1") (pintype "passive"))
      (node (ref "D4") (pin "P$1") (pinfunction "C_P$1") (pintype "passive"))
      (node (ref "D6") (pin "A") (pinfunction "A_A") (pintype "passive"))
      (node (ref "IC2") (pin "1") (pinfunction "OUT_1") (pintype "output"))
      (node (ref "R32") (pin "2") (pinfunction "2_2") (pintype "passive"))
      (node (ref "VR1B") (pin "2") (pinfunction "2_2") (pintype "passive"))
      (node (ref "VR1B") (pin "3") (pinfunction "3_3") (pintype "passive"))
    )
    (net (code "33") (name "Net-(D7-A)") (class "Default")
      (node (ref "D6") (pin "C") (pinfunction "C_C") (pintype "passive"))
      (node (ref "D7") (pin "ANODE") (pinfunction "A_ANODE") (pintype "passive"))
    )
    (net (code "34") (name "Net-(D11-PadA)") (class "Default")
      (node (ref "D11") (pin "A") (pinfunction "A_A") (pintype "passive"))
      (node (ref "D16") (pin "C") (pinfunction "C_C") (pintype "passive"))
    )
    (net (code "35") (name "Net-(D14-A)") (class "Default")
      (node (ref "C37") (pin "2") (pinfunction "2_2") (pintype "passive"))
      (node (ref "D14") (pin "ANODE") (pinfunction "A_ANODE") (pintype "passive"))
      (node (ref "D15") (pin "P$1") (pinfunction "C_P$1") (pintype "passive"))
      (node (ref "R52") (pin "1") (pinfunction "1_1") (pintype "passive"))
      (node (ref "R53") (pin "2") (pinfunction "2_2") (pintype "passive"))
    )
    (net (code "36") (name "Net-(GREEN-A)") (class "Default")
      (node (ref "GREEN") (pin "ANODE") (pinfunction "A_ANODE") (pintype "passive"))
      (node (ref "R9") (pin "2") (pinfunction "2_2") (pintype "passive"))
    )
    (net (code "37") (name "Net-(GREEN-C)") (class "Default")
      (node (ref "D1") (pin "A") (pinfunction "A_A") (pintype "passive"))
      (node (ref "GREEN") (pin "P$1") (pinfunction "C_P$1") (pintype "passive"))
      (node (ref "RED") (pin "P$1") (pinfunction "C_P$1") (pintype "passive"))
    )
    (net (code "38") (name "Net-(IC1A-I0)") (class "Default")
      (node (ref "IC1") (pin "1") (pinfunction "I0_1") (pintype "input"))
      (node (ref "IC1") (pin "2") (pinfunction "I1_2") (pintype "input"))
      (node (ref "IC1") (pin "6") (pinfunction "I1_6") (pintype "input"))
      (node (ref "IC1") (pin "9") (pinfunction "I1_9") (pintype "input"))
      (node (ref "R21") (pin "2") (pinfunction "2_2") (pintype "passive"))
      (node (ref "SW1") (pin "C") (pinfunction "A_C") (pintype "bidirectional"))
    )
    (net (code "39") (name "Net-(IC1A-O)") (class "Default")
      (node (ref "IC1") (pin "3") (pinfunction "O_3") (pintype "output"))
      (node (ref "R6") (pin "2") (pinfunction "2_2") (pintype "passive"))
    )
    (net (code "40") (name "Net-(IC1B-I0)") (class "Default")
      (node (ref "IC1") (pin "11") (pinfunction "O_11") (pintype "output"))
      (node (ref "IC1") (pin "5") (pinfunction "I0_5") (pintype "input"))
    )
    (net (code "41") (name "Net-(IC1B-O)") (class "Default")
      (node (ref "IC1") (pin "4") (pinfunction "O_4") (pintype "output"))
      (node (ref "Q3") (pin "2") (pinfunction "B_2") (pintype "passive"))
      (node (ref "Q5") (pin "2") (pinfunction "B_2") (pintype "passive"))
    )
    (net (code "42") (name "Net-(IC1C-I0)") (class "Default")
      (node (ref "IC1") (pin "12") (pinfunction "I0_12") (pintype "input"))
      (node (ref "IC1") (pin "13") (pinfunction "I1_13") (pintype "input"))
      (node (ref "IC1") (pin "8") (pinfunction "I0_8") (pintype "input"))
      (node (ref "R13") (pin "2") (pinfunction "2_2") (pintype "passive"))
      (node (ref "SW1") (pin "9") (pinfunction "A_9") (pintype "bidirectional"))
    )
    (net (code "43") (name "Net-(IC1C-O)") (class "Default")
      (node (ref "IC1") (pin "10") (pinfunction "O_10") (pintype "output"))
      (node (ref "Q4") (pin "2") (pinfunction "B_2") (pintype "passive"))
      (node (ref "Q6") (pin "2") (pinfunction "B_2") (pintype "passive"))
    )
    (net (code "44") (name "Net-(IC2A-+IN)") (class "Default")
      (node (ref "C48") (pin "1") (pinfunction "1_1") (pintype "passive"))
      (node (ref "IC2") (pin "3") (pinfunction "+IN_3") (pintype "input"))
      (node (ref "R51") (pin "1") (pinfunction "1_1") (pintype "passive"))
    )
    (net (code "45") (name "Net-(IC2B-+IN)") (class "Default")
      (node (ref "C13") (pin "1") (pinfunction "1_1") (pintype "passive"))
      (node (ref "IC2") (pin "5") (pinfunction "+IN_5") (pintype "input"))
      (node (ref "R35") (pin "1") (pinfunction "1_1") (pintype "passive"))
    )
    (net (code "46") (name "Net-(IC2B--IN)") (class "Default")
      (node (ref "C14") (pin "2") (pinfunction "2_2") (pintype "passive"))
      (node (ref "C16") (pin "1") (pinfunction "1_1") (pintype "passive"))
      (node (ref "IC2") (pin "6") (pinfunction "-IN_6") (pintype "input"))
      (node (ref "R25") (pin "2") (pinfunction "2_2") (pintype "passive"))
    )
    (net (code "47") (name "Net-(IC2B-OUT)") (class "Default")
      (node (ref "C14") (pin "1") (pinfunction "1_1") (pintype "passive"))
      (node (ref "C9") (pin "2") (pinfunction "2_2") (pintype "passive"))
      (node (ref "IC2") (pin "7") (pinfunction "OUT_7") (pintype "output"))
      (node (ref "R25") (pin "1") (pinfunction "1_1") (pintype "passive"))
    )
    (net (code "48") (name "Net-(IC3A--IN)") (class "Default")
      (node (ref "C20") (pin "2") (pinfunction "2_2") (pintype "passive"))
      (node (ref "IC3") (pin "2") (pinfunction "-IN_2") (pintype "input"))
      (node (ref "R29") (pin "2") (pinfunction "2_2") (pintype "passive"))
      (node (ref "R38") (pin "1") (pinfunction "1_1") (pintype "passive"))
    )
    (net (code "49") (name "Net-(IC3A-OUT)") (class "Default")
      (node (ref "C20") (pin "1") (pinfunction "1_1") (pintype "passive"))
      (node (ref "C30") (pin "+") (pinfunction "+_+") (pintype "passive"))
      (node (ref "IC3") (pin "1") (pinfunction "OUT_1") (pintype "output"))
      (node (ref "R29") (pin "1") (pinfunction "1_1") (pintype "passive"))
    )
    (net (code "50") (name "Net-(IC3B-+IN)") (class "Default")
      (node (ref "C9") (pin "1") (pinfunction "1_1") (pintype "passive"))
      (node (ref "IC3") (pin "5") (pinfunction "+IN_5") (pintype "input"))
      (node (ref "R27") (pin "1") (pinfunction "1_1") (pintype "passive"))
    )
    (net (code "51") (name "Net-(IC3B--IN)") (class "Default")
      (node (ref "C19") (pin "2") (pinfunction "2_2") (pintype "passive"))
      (node (ref "IC3") (pin "6") (pinfunction "-IN_6") (pintype "input"))
      (node (ref "R28") (pin "1") (pinfunction "1_1") (pintype "passive"))
      (node (ref "VR1A") (pin "1") (pinfunction "1_1") (pintype "passive"))
    )
    (net (code "52") (name "Net-(IC3B-OUT)") (class "Default")
      (node (ref "C18") (pin "2") (pinfunction "2_2") (pintype "passive"))
      (node (ref "C19") (pin "1") (pinfunction "1_1") (pintype "passive"))
      (node (ref "IC3") (pin "7") (pinfunction "OUT_7") (pintype "output"))
      (node (ref "VR1A") (pin "2") (pinfunction "2_2") (pintype "passive"))
      (node (ref "VR1A") (pin "3") (pinfunction "3_3") (pintype "passive"))
    )
    (net (code "53") (name "Net-(IC4A-+IN)") (class "Default")
      (node (ref "C40") (pin "+") (pinfunction "+_+") (pintype "passive"))
      (node (ref "IC4") (pin "3") (pinfunction "+IN_3") (pintype "input"))
      (node (ref "R57") (pin "1") (pinfunction "1_1") (pintype "passive"))
    )
    (net (code "54") (name "Net-(IC4A--IN)") (class "Default")
      (node (ref "C41") (pin "2") (pinfunction "2_2") (pintype "passive"))
      (node (ref "D10") (pin "A") (pinfunction "A_A") (pintype "passive"))
      (node (ref "D11") (pin "C") (pinfunction "C_C") (pintype "passive"))
      (node (ref "IC4") (pin "2") (pinfunction "-IN_2") (pintype "input"))
      (node (ref "R59") (pin "2") (pinfunction "2_2") (pintype "passive"))
      (node (ref "R60") (pin "1") (pinfunction "1_1") (pintype "passive"))
    )
    (net (code "55") (name "Net-(IC4A-OUT)") (class "Default")
      (node (ref "C41") (pin "1") (pinfunction "1_1") (pintype "passive"))
      (node (ref "D10") (pin "C") (pinfunction "C_C") (pintype "passive"))
      (node (ref "D16") (pin "A") (pinfunction "A_A") (pintype "passive"))
      (node (ref "IC4") (pin "1") (pinfunction "OUT_1") (pintype "output"))
      (node (ref "R59") (pin "1") (pinfunction "1_1") (pintype "passive"))
      (node (ref "R64") (pin "2") (pinfunction "2_2") (pintype "passive"))
    )
    (net (code "56") (name "Net-(IC4B--IN)") (class "Default")
      (node (ref "C42") (pin "2") (pinfunction "2_2") (pintype "passive"))
      (node (ref "IC4") (pin "6") (pinfunction "-IN_6") (pintype "input"))
      (node (ref "R39") (pin "1") (pinfunction "1_1") (pintype "passive"))
      (node (ref "R58") (pin "2") (pinfunction "2_2") (pintype "passive"))
    )
    (net (code "57") (name "Net-(IC4B-OUT)") (class "Default")
      (node (ref "C42") (pin "1") (pinfunction "1_1") (pintype "passive"))
      (node (ref "C43") (pin "2") (pinfunction "2_2") (pintype "passive"))
      (node (ref "IC4") (pin "7") (pinfunction "OUT_7") (pintype "output"))
      (node (ref "R58") (pin "1") (pinfunction "1_1") (pintype "passive"))
    )
    (net (code "58") (name "Net-(Q1-B)") (class "Default")
      (node (ref "C11") (pin "2") (pinfunction "2_2") (pintype "passive"))
      (node (ref "C6") (pin "1") (pinfunction "1_1") (pintype "passive"))
      (node (ref "Q1") (pin "1") (pinfunction "B_1") (pintype "passive"))
      (node (ref "R18") (pin "2") (pinfunction "2_2") (pintype "passive"))
      (node (ref "R7") (pin "1") (pinfunction "1_1") (pintype "passive"))
    )
    (net (code "59") (name "Net-(Q1-C)") (class "Default")
      (node (ref "C7") (pin "2") (pinfunction "2_2") (pintype "passive"))
      (node (ref "Q1") (pin "2") (pinfunction "C_2") (pintype "passive"))
      (node (ref "R11") (pin "1") (pinfunction "1_1") (pintype "passive"))
      (node (ref "R3") (pin "1") (pinfunction "1_1") (pintype "passive"))
    )
    (net (code "60") (name "Net-(Q2-B)") (class "Default")
      (node (ref "C3") (pin "1") (pinfunction "1_1") (pintype "passive"))
      (node (ref "C7") (pin "1") (pinfunction "1_1") (pintype "passive"))
      (node (ref "Q2") (pin "1") (pinfunction "B_1") (pintype "passive"))
      (node (ref "R3") (pin "2") (pinfunction "2_2") (pintype "passive"))
      (node (ref "R4") (pin "2") (pinfunction "2_2") (pintype "passive"))
    )
    (net (code "61") (name "Net-(Q2-C)") (class "Default")
      (node (ref "C11") (pin "1") (pinfunction "1_1") (pintype "passive"))
      (node (ref "Q2") (pin "2") (pinfunction "C_2") (pintype "passive"))
      (node (ref "R19") (pin "1") (pinfunction "1_1") (pintype "passive"))
      (node (ref "R5") (pin "1") (pinfunction "1_1") (pintype "passive"))
      (node (ref "R7") (pin "2") (pinfunction "2_2") (pintype "passive"))
    )
    (net (code "62") (name "Net-(Q3-C)") (class "Default")
      (node (ref "Q3") (pin "1") (pinfunction "C_1") (pintype "passive"))
      (node (ref "R14") (pin "2") (pinfunction "2_2") (pintype "passive"))
      (node (ref "R8") (pin "1") (pinfunction "1_1") (pintype "passive"))
    )
    (net (code "63") (name "Net-(Q4-C)") (class "Default")
      (node (ref "Q4") (pin "1") (pinfunction "C_1") (pintype "passive"))
      (node (ref "R9") (pin "1") (pinfunction "1_1") (pintype "passive"))
    )
    (net (code "64") (name "Net-(Q5-C)") (class "Default")
      (node (ref "Q5") (pin "1") (pinfunction "C_1") (pintype "passive"))
      (node (ref "R10") (pin "1") (pinfunction "1_1") (pintype "passive"))
    )
    (net (code "65") (name "Net-(Q6-C)") (class "Default")
      (node (ref "Q6") (pin "1") (pinfunction "C_1") (pintype "passive"))
      (node (ref "R22") (pin "1") (pinfunction "1_1") (pintype "passive"))
      (node (ref "R24") (pin "2") (pinfunction "2_2") (pintype "passive"))
    )
    (net (code "66") (name "Net-(Q7-B)") (class "Default")
      (node (ref "C17") (pin "2") (pinfunction "2_2") (pintype "passive"))
      (node (ref "Q7") (pin "2") (pinfunction "B_2") (pintype "passive"))
      (node (ref "R26") (pin "2") (pinfunction "2_2") (pintype "passive"))
    )
    (net (code "67") (name "Net-(Q7-E)") (class "Default")
      (node (ref "Q7") (pin "3") (pinfunction "E_3") (pintype "passive"))
      (node (ref "R15") (pin "2") (pinfunction "2_2") (pintype "passive"))
      (node (ref "R16") (pin "1") (pinfunction "1_1") (pintype "passive"))
    )
    (net (code "68") (name "Net-(Q8-D)") (class "Default")
      (node (ref "C26") (pin "-") (pinfunction "-_-") (pintype "passive"))
      (node (ref "Q8") (pin "3") (pinfunction "D_3") (pintype "passive"))
      (node (ref "R33") (pin "1") (pinfunction "1_1") (pintype "passive"))
    )
    (net (code "69") (name "Net-(Q8-G)") (class "Default")
      (node (ref "D3") (pin "A") (pinfunction "A_A") (pintype "passive"))
      (node (ref "Q8") (pin "1") (pinfunction "G_1") (pintype "passive"))
    )
    (net (code "70") (name "Net-(Q8-S)") (class "Default")
      (node (ref "C13") (pin "2") (pinfunction "2_2") (pintype "passive"))
      (node (ref "Q8") (pin "2") (pinfunction "S_2") (pintype "passive"))
      (node (ref "R34") (pin "1") (pinfunction "1_1") (pintype "passive"))
    )
    (net (code "71") (name "Net-(Q9-D)") (class "Default")
      (node (ref "C35") (pin "+") (pinfunction "+_+") (pintype "passive"))
      (node (ref "Q9") (pin "3") (pinfunction "D_3") (pintype "passive"))
      (node (ref "R42") (pin "1") (pinfunction "1_1") (pintype "passive"))
    )
    (net (code "72") (name "Net-(Q9-G)") (class "Default")
      (node (ref "D5") (pin "A") (pinfunction "A_A") (pintype "passive"))
      (node (ref "Q9") (pin "1") (pinfunction "G_1") (pintype "passive"))
    )
    (net (code "73") (name "Net-(Q10-B)") (class "Default")
      (node (ref "C22") (pin "1") (pinfunction "1_1") (pintype "passive"))
      (node (ref "Q10") (pin "2") (pinfunction "B_2") (pintype "passive"))
      (node (ref "R41") (pin "1") (pinfunction "1_1") (pintype "passive"))
    )
    (net (code "74") (name "Net-(Q10-E)") (class "Default")
      (node (ref "C21") (pin "+") (pinfunction "+_+") (pintype "passive"))
      (node (ref "Q10") (pin "3") (pinfunction "E_3") (pintype "passive"))
      (node (ref "R31") (pin "1") (pinfunction "1_1") (pintype "passive"))
    )
    (net (code "75") (name "Net-(Q11-D)") (class "Default")
      (node (ref "C25") (pin "+") (pinfunction "+_+") (pintype "passive"))
      (node (ref "Q11") (pin "3") (pinfunction "D_3") (pintype "passive"))
      (node (ref "R43") (pin "1") (pinfunction "1_1") (pintype "passive"))
    )
    (net (code "76") (name "Net-(Q11-G)") (class "Default")
      (node (ref "D8") (pin "A") (pinfunction "A_A") (pintype "passive"))
      (node (ref "Q11") (pin "1") (pinfunction "G_1") (pintype "passive"))
    )
    (net (code "77") (name "Net-(Q11-S)") (class "Default")
      (node (ref "C22") (pin "2") (pinfunction "2_2") (pintype "passive"))
      (node (ref "Q11") (pin "2") (pinfunction "S_2") (pintype "passive"))
    )
    (net (code "78") (name "Net-(Q12-B)") (class "Default")
      (node (ref "C26") (pin "+") (pinfunction "+_+") (pintype "passive"))
      (node (ref "C46") (pin "+") (pinfunction "+_+") (pintype "passive"))
      (node (ref "Q12") (pin "2") (pinfunction "B_2") (pintype "passive"))
      (node (ref "Q14") (pin "2") (pinfunction "S_2") (pintype "passive"))
      (node (ref "R46") (pin "1") (pinfunction "1_1") (pintype "passive"))
    )
    (net (code "79") (name "Net-(Q12-E)") (class "Default")
      (node (ref "C35") (pin "-") (pinfunction "-_-") (pintype "passive"))
      (node (ref "Q12") (pin "3") (pinfunction "E_3") (pintype "passive"))
      (node (ref "R47") (pin "1") (pinfunction "1_1") (pintype "passive"))
    )
    (net (code "80") (name "Net-(Q13-D)") (class "Default")
      (node (ref "C27") (pin "+") (pinfunction "+_+") (pintype "passive"))
      (node (ref "Q13") (pin "3") (pinfunction "D_3") (pintype "passive"))
      (node (ref "R48") (pin "1") (pinfunction "1_1") (pintype "passive"))
    )
    (net (code "81") (name "Net-(Q13-G)") (class "Default")
      (node (ref "D9") (pin "A") (pinfunction "A_A") (pintype "passive"))
      (node (ref "Q13") (pin "1") (pinfunction "G_1") (pintype "passive"))
    )
    (net (code "82") (name "Net-(Q13-S)") (class "Default")
      (node (ref "Q13") (pin "2") (pinfunction "S_2") (pintype "passive"))
      (node (ref "Q9") (pin "2") (pinfunction "S_2") (pintype "passive"))
      (node (ref "R45") (pin "1") (pinfunction "1_1") (pintype "passive"))
    )
    (net (code "83") (name "Net-(Q14-G)") (class "Default")
      (node (ref "C34") (pin "1") (pinfunction "1_1") (pintype "passive"))
      (node (ref "Q14") (pin "1") (pinfunction "G_1") (pintype "passive"))
      (node (ref "R63") (pin "1") (pinfunction "1_1") (pintype "passive"))
    )
    (net (code "84") (name "Net-(Q15-D)") (class "Default")
      (node (ref "C46") (pin "-") (pinfunction "-_-") (pintype "passive"))
      (node (ref "Q15") (pin "3") (pinfunction "D_3") (pintype "passive"))
      (node (ref "R65") (pin "1") (pinfunction "1_1") (pintype "passive"))
    )
    (net (code "85") (name "Net-(Q15-G)") (class "Default")
      (node (ref "D13") (pin "A") (pinfunction "A_A") (pintype "passive"))
      (node (ref "Q15") (pin "1") (pinfunction "G_1") (pintype "passive"))
    )
    (net (code "86") (name "Net-(Q15-S)") (class "Default")
      (node (ref "C36") (pin "2") (pinfunction "2_2") (pintype "passive"))
      (node (ref "Q15") (pin "2") (pinfunction "S_2") (pintype "passive"))
      (node (ref "R50") (pin "1") (pinfunction "1_1") (pintype "passive"))
    )
    (net (code "87") (name "Net-(R36-Pad1)") (class "Default")
      (node (ref "R36") (pin "1") (pinfunction "1_1") (pintype "passive"))
      (node (ref "VR1B") (pin "1") (pinfunction "1_1") (pintype "passive"))
    )
    (net (code "88") (name "Net-(R90-Pad2)") (class "Default")
      (node (ref "R90") (pin "2") (pinfunction "2_2") (pintype "passive"))
      (node (ref "VR3A") (pin "2") (pinfunction "2_2") (pintype "passive"))
    )
    (net (code "89") (name "Net-(RED-A)") (class "Default")
      (node (ref "R10") (pin "2") (pinfunction "2_2") (pintype "passive"))
      (node (ref "RED") (pin "ANODE") (pinfunction "A_ANODE") (pintype "passive"))
    )
    (net (code "90") (name "Net-(REMOTE-TIP)") (class "Default")
      (node (ref "REMOTE") (pin "T") (pinfunction "TIP_T") (pintype "passive"))
      (node (ref "SW1") (pin "7") (pinfunction "3_7") (pintype "bidirectional"))
    )
    (net (code "91") (name "Net-(SW1B-1)") (class "Default")
      (node (ref "C4") (pin "1") (pinfunction "1_1") (pintype "passive"))
      (node (ref "R5") (pin "2") (pinfunction "2_2") (pintype "passive"))
      (node (ref "SW1") (pin "2") (pinfunction "2_2") (pintype "bidirectional"))
      (node (ref "SW1") (pin "3") (pinfunction "3_3") (pintype "bidirectional"))
      (node (ref "SW1") (pin "5") (pinfunction "1_5") (pintype "bidirectional"))
    )
    (net (code "92") (name "Net-(SW2-P)") (class "Default")
      (node (ref "R2") (pin "2") (pinfunction "2_2") (pintype "passive"))
      (node (ref "SW2") (pin "1") (pinfunction "P_1") (pintype "passive"))
    )
    (net (code "93") (name "Net-(VR2A-Pad2)") (class "Default")
      (node (ref "VR2A") (pin "2") (pinfunction "2_2") (pintype "passive"))
      (node (ref "VR3A") (pin "3") (pinfunction "3_3") (pintype "passive"))
    )
    (net (code "94") (name "Net-(VR2B-Pad2)") (class "Default")
      (node (ref "VR2B") (pin "2") (pinfunction "2_2") (pintype "passive"))
      (node (ref "VR3B") (pin "3") (pinfunction "3_3") (pintype "passive"))
    )
    (net (code "95") (name "OUT") (class "Default")
      (node (ref "R40") (pin "1") (pinfunction "1_1") (pintype "passive"))
    )
    (net (code "96") (name "VB") (class "Default")
      (node (ref "C45") (pin "+") (pinfunction "+_+") (pintype "passive"))
      (node (ref "IC3") (pin "3") (pinfunction "+IN_3") (pintype "input"))
      (node (ref "IC4") (pin "5") (pinfunction "+IN_5") (pintype "input"))
      (node (ref "R26") (pin "1") (pinfunction "1_1") (pintype "passive"))
      (node (ref "R27") (pin "2") (pinfunction "2_2") (pintype "passive"))
      (node (ref "R33") (pin "2") (pinfunction "2_2") (pintype "passive"))
      (node (ref "R34") (pin "2") (pinfunction "2_2") (pintype "passive"))
      (node (ref "R35") (pin "2") (pinfunction "2_2") (pintype "passive"))
      (node (ref "R41") (pin "2") (pinfunction "2_2") (pintype "passive"))
      (node (ref "R42") (pin "2") (pinfunction "2_2") (pintype "passive"))
      (node (ref "R43") (pin "2") (pinfunction "2_2") (pintype "passive"))
      (node (ref "R44") (pin "1") (pinfunction "1_1") (pintype "passive"))
      (node (ref "R45") (pin "2") (pinfunction "2_2") (pintype "passive"))
      (node (ref "R48") (pin "2") (pinfunction "2_2") (pintype "passive"))
      (node (ref "R50") (pin "2") (pinfunction "2_2") (pintype "passive"))
      (node (ref "R51") (pin "2") (pinfunction "2_2") (pintype "passive"))
      (node (ref "R57") (pin "2") (pinfunction "2_2") (pintype "passive"))
      (node (ref "R61") (pin "1") (pinfunction "1_1") (pintype "passive"))
      (node (ref "R63") (pin "2") (pinfunction "2_2") (pintype "passive"))
      (node (ref "R65") (pin "2") (pinfunction "2_2") (pintype "passive"))
    )
    (net (code "97") (name "unconnected-(SW1-Pad1)") (class "Default")
      (node (ref "SW1") (pin "1") (pinfunction "1_1") (pintype "bidirectional"))
    )
    (net (code "98") (name "unconnected-(SW1-Pad4)") (class "Default")
      (node (ref "SW1") (pin "4") (pinfunction "4_4") (pintype "bidirectional"))
    )
    (net (code "99") (name "unconnected-(SW1B-4-Pad8)") (class "Default")
      (node (ref "SW1") (pin "8") (pinfunction "4_8") (pintype "bidirectional"))
    )
  )
)
